# Driving.net
KiCad netlist of a schematic drawn in Altium Designer
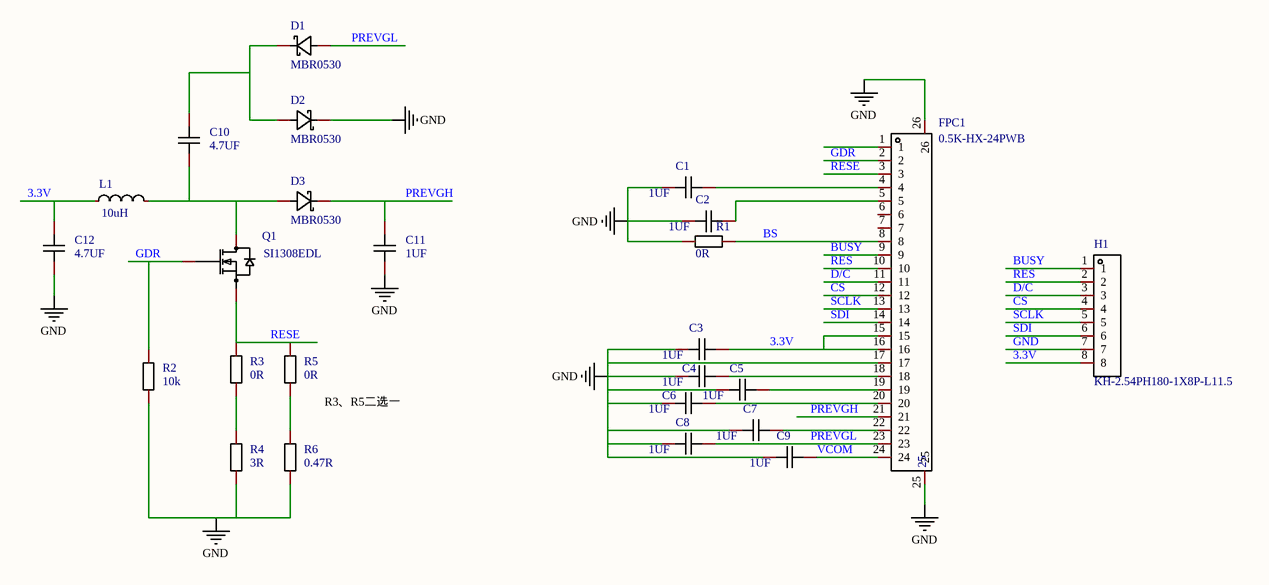
[diagram p0: Driving .schdoc]

(export (version "E")
  (design (tool "Eeschema 10.0.6"))
  (components
    (comp (ref "C1")
      (value "1UF")
      (fields (field (name "NAME") "1UF"))
      (libsource (lib "altium-import") (part "root_0_CAP_0603_"))
    )
    (comp (ref "C2")
      (value "1UF")
      (fields (field (name "NAME") "1UF"))
      (libsource (lib "altium-import") (part "root_0_CAP_0603_"))
    )
    (comp (ref "C3")
      (value "1UF")
      (fields (field (name "NAME") "1UF"))
      (libsource (lib "altium-import") (part "root_0_CAP_0603_"))
    )
    (comp (ref "C4")
      (value "1UF")
      (fields (field (name "NAME") "1UF"))
      (libsource (lib "altium-import") (part "root_0_CAP_0603_"))
    )
    (comp (ref "C5")
      (value "1UF")
      (fields (field (name "NAME") "1UF"))
      (libsource (lib "altium-import") (part "root_0_CAP_0603_"))
    )
    (comp (ref "C6")
      (value "1UF")
      (fields (field (name "NAME") "1UF"))
      (libsource (lib "altium-import") (part "root_0_CAP_0603_"))
    )
    (comp (ref "C7")
      (value "1UF")
      (fields (field (name "NAME") "1UF"))
      (libsource (lib "altium-import") (part "root_0_CAP_0603_"))
    )
    (comp (ref "C8")
      (value "1UF")
      (fields (field (name "NAME") "1UF"))
      (libsource (lib "altium-import") (part "root_0_CAP_0603_"))
    )
    (comp (ref "C9")
      (value "1UF")
      (fields (field (name "NAME") "1UF"))
      (libsource (lib "altium-import") (part "root_0_CAP_0603_"))
    )
    (comp (ref "C10")
      (value "4.7UF")
      (fields (field (name "NAME") "4.7UF"))
      (libsource (lib "altium-import") (part "root_1_CAP_0603_"))
    )
    (comp (ref "C11")
      (value "1UF")
      (fields (field (name "NAME") "1UF"))
      (libsource (lib "altium-import") (part "root_1_CAP_0603_"))
    )
    (comp (ref "C12")
      (value "4.7UF")
      (fields (field (name "NAME") "4.7UF"))
      (libsource (lib "altium-import") (part "root_1_CAP_0603_"))
    )
    (comp (ref "D1")
      (value "MBR0530")
      (description "直流反向耐压(Vr):30V;平均整流电流(Io):500mA;正向压降(Vf):550mV@500mA;")
      (fields (field (name "NAME") "MBR0530") (field (name "MANUFACTURER") "YANGJIE(扬杰)"))
      (libsource (lib "altium-import") (part "root_0_MBR0530_C699108_"))
    )
    (comp (ref "D2")
      (value "MBR0530")
      (description "直流反向耐压(Vr):30V;平均整流电流(Io):500mA;正向压降(Vf):550mV@500mA;")
      (fields (field (name "NAME") "MBR0530") (field (name "MANUFACTURER") "YANGJIE(扬杰)"))
      (libsource (lib "altium-import") (part "root_2_MBR0530_C699108_"))
    )
    (comp (ref "D3")
      (value "MBR0530")
      (description "直流反向耐压(Vr):30V;平均整流电流(Io):500mA;正向压降(Vf):550mV@500mA;")
      (fields (field (name "NAME") "MBR0530") (field (name "MANUFACTURER") "YANGJIE(扬杰)"))
      (libsource (lib "altium-import") (part "root_2_MBR0530_C699108_"))
    )
    (comp (ref "FPC1")
      (value "0.5K-HX-24PWB")
      (description "间距:0.5mm;触点数量:24;锁定特性:翻盖式;安装类型:卧贴;触点类型:双侧触点/上下接;工作温度范围:-55~+85;")
      (fields
        (field (name "NAME") "0.5K-HX-24PWB")
        (field (name "MANUFACTURER") "HDGC(华德共创)")
        (field (name "NAME_1") "25")
      )
      (libsource (lib "altium-import") (part "root_0_0.5K-HX-24PWB_"))
    )
    (comp (ref "H1")
      (value "KH-2.54PH180-1X8P-L11.5")
      (fields (field (name "NAME") "KH-2.54PH180-1X8P-L11.5") (field (name "MANUFACTURER") "kinghelm(金航标)"))
      (libsource (lib "altium-import") (part "root_0_KH-2.54PH180-1X8P-L11.5_"))
    )
    (comp (ref "L1")
      (value "10uH")
      (description "电感值:10uH;精度:±20%;额定电流:1A;直流电阻(DCR):85mΩ;")
      (fields
        (field (name "NAME") "10uH")
        (field (name "MANUFACTURER") "YJYCOIN(益嘉源)")
        (field (name "MANUFACTURER PART") "YNR4026-100M")
      )
      (libsource (lib "altium-import") (part "root_0_YNR4026-100M_"))
    )
    (comp (ref "Q1")
      (value "SI1308EDL")
      (description "类型:N沟道;漏源电压(Vdss):20V;连续漏极电流(Id):4A;导通电阻(RDS(on)@Vgs,Id):36mΩ@10V,4A;")
      (fields (field (name "NAME") "SI1308EDL") (field (name "MANUFACTURER") "VBsemi(微碧)"))
      (libsource (lib "altium-import") (part "root_0_SI1308EDL_"))
    )
    (comp (ref "R1")
      (value "0R")
      (fields (field (name "NAME") "0R"))
      (libsource (lib "altium-import") (part "root_0_Res_0603_"))
    )
    (comp (ref "R2")
      (value "10k")
      (fields (field (name "NAME") "10k"))
      (libsource (lib "altium-import") (part "root_1_Res_0603_"))
    )
    (comp (ref "R3")
      (value "0R")
      (fields (field (name "NAME") "0R"))
      (libsource (lib "altium-import") (part "root_1_Res_0603_"))
    )
    (comp (ref "R4")
      (value "3R")
      (fields (field (name "NAME") "3R"))
      (libsource (lib "altium-import") (part "root_1_Res_0603_"))
    )
    (comp (ref "R5")
      (value "0R")
      (fields (field (name "NAME") "0R"))
      (libsource (lib "altium-import") (part "root_1_Res_0603_"))
    )
    (comp (ref "R6")
      (value "0.47R")
      (fields (field (name "NAME") "0.47R"))
      (libsource (lib "altium-import") (part "root_1_Res_0603_"))
    )
  )
  (nets
    (net (code "1") (name "/3.3V") (class "Default")
      (node (ref "C12") (pin "2") (pinfunction "2_2") (pintype "passive"))
      (node (ref "C3") (pin "2") (pinfunction "2_2") (pintype "passive"))
      (node (ref "FPC1") (pin "15") (pinfunction "15_15") (pintype "passive"))
      (node (ref "FPC1") (pin "16") (pinfunction "16_16") (pintype "passive"))
      (node (ref "H1") (pin "8") (pinfunction "8_8") (pintype "passive"))
      (node (ref "L1") (pin "1") (pinfunction "1_1") (pintype "passive"))
    )
    (net (code "2") (name "/BS") (class "Default")
      (node (ref "FPC1") (pin "8") (pinfunction "8_8") (pintype "passive"))
      (node (ref "R1") (pin "2") (pinfunction "2_2") (pintype "passive"))
    )
    (net (code "3") (name "/BUSY") (class "Default")
      (node (ref "FPC1") (pin "9") (pinfunction "9_9") (pintype "passive"))
      (node (ref "H1") (pin "1") (pinfunction "1_1") (pintype "passive"))
    )
    (net (code "4") (name "/CS") (class "Default")
      (node (ref "FPC1") (pin "12") (pinfunction "12_12") (pintype "passive"))
      (node (ref "H1") (pin "4") (pinfunction "4_4") (pintype "passive"))
    )
    (net (code "5") (name "/D{slash}C") (class "Default")
      (node (ref "FPC1") (pin "11") (pinfunction "11_11") (pintype "passive"))
      (node (ref "H1") (pin "3") (pinfunction "3_3") (pintype "passive"))
    )
    (net (code "6") (name "/GDR") (class "Default")
      (node (ref "FPC1") (pin "2") (pinfunction "2_2") (pintype "passive"))
      (node (ref "Q1") (pin "1") (pinfunction "G_1") (pintype "passive"))
      (node (ref "R2") (pin "2") (pinfunction "2_2") (pintype "passive"))
    )
    (net (code "7") (name "/PREVGH") (class "Default")
      (node (ref "C11") (pin "2") (pinfunction "2_2") (pintype "passive"))
      (node (ref "D3") (pin "1") (pinfunction "K_1") (pintype "passive"))
      (node (ref "FPC1") (pin "21") (pinfunction "21_21") (pintype "passive"))
    )
    (net (code "8") (name "/PREVGL") (class "Default")
      (node (ref "C8") (pin "2") (pinfunction "2_2") (pintype "passive"))
      (node (ref "D1") (pin "2") (pinfunction "A_2") (pintype "passive"))
      (node (ref "FPC1") (pin "23") (pinfunction "23_23") (pintype "passive"))
    )
    (net (code "9") (name "/RES") (class "Default")
      (node (ref "FPC1") (pin "10") (pinfunction "10_10") (pintype "passive"))
      (node (ref "H1") (pin "2") (pinfunction "2_2") (pintype "passive"))
    )
    (net (code "10") (name "/RESE") (class "Default")
      (node (ref "FPC1") (pin "3") (pinfunction "3_3") (pintype "passive"))
      (node (ref "Q1") (pin "2") (pinfunction "S_2") (pintype "passive"))
      (node (ref "R3") (pin "2") (pinfunction "2_2") (pintype "passive"))
      (node (ref "R5") (pin "2") (pinfunction "2_2") (pintype "passive"))
    )
    (net (code "11") (name "/SCLK") (class "Default")
      (node (ref "FPC1") (pin "13") (pinfunction "13_13") (pintype "passive"))
      (node (ref "H1") (pin "5") (pinfunction "5_5") (pintype "passive"))
    )
    (net (code "12") (name "/SDI") (class "Default")
      (node (ref "FPC1") (pin "14") (pinfunction "14_14") (pintype "passive"))
      (node (ref "H1") (pin "6") (pinfunction "6_6") (pintype "passive"))
    )
    (net (code "13") (name "/VCOM") (class "Default")
      (node (ref "C9") (pin "2") (pinfunction "2_2") (pintype "passive"))
      (node (ref "FPC1") (pin "24") (pinfunction "24_24") (pintype "passive"))
    )
    (net (code "14") (name "GND") (class "Default")
      (node (ref "C1") (pin "1") (pinfunction "1_1") (pintype "passive"))
      (node (ref "C11") (pin "1") (pinfunction "1_1") (pintype "passive"))
      (node (ref "C12") (pin "1") (pinfunction "1_1") (pintype "passive"))
      (node (ref "C2") (pin "1") (pinfunction "1_1") (pintype "passive"))
      (node (ref "C3") (pin "1") (pinfunction "1_1") (pintype "passive"))
      (node (ref "C4") (pin "1") (pinfunction "1_1") (pintype "passive"))
      (node (ref "C5") (pin "1") (pinfunction "1_1") (pintype "passive"))
      (node (ref "C6") (pin "1") (pinfunction "1_1") (pintype "passive"))
      (node (ref "C7") (pin "1") (pinfunction "1_1") (pintype "passive"))
      (node (ref "C8") (pin "1") (pinfunction "1_1") (pintype "passive"))
      (node (ref "C9") (pin "1") (pinfunction "1_1") (pintype "passive"))
      (node (ref "D2") (pin "1") (pinfunction "K_1") (pintype "passive"))
      (node (ref "FPC1") (pin "17") (pinfunction "17_17") (pintype "passive"))
      (node (ref "FPC1") (pin "25") (pinfunction "25_25") (pintype "passive"))
      (node (ref "FPC1") (pin "26") (pinfunction "26_26") (pintype "passive"))
      (node (ref "H1") (pin "7") (pinfunction "7_7") (pintype "passive"))
      (node (ref "R1") (pin "1") (pinfunction "1_1") (pintype "passive"))
      (node (ref "R2") (pin "1") (pinfunction "1_1") (pintype "passive"))
      (node (ref "R4") (pin "1") (pinfunction "1_1") (pintype "passive"))
      (node (ref "R6") (pin "1") (pinfunction "1_1") (pintype "passive"))
    )
    (net (code "15") (name "Net-(C1-Pad2)") (class "Default")
      (node (ref "C1") (pin "2") (pinfunction "2_2") (pintype "passive"))
      (node (ref "FPC1") (pin "4") (pinfunction "4_4") (pintype "passive"))
    )
    (net (code "16") (name "Net-(C2-Pad2)") (class "Default")
      (node (ref "C2") (pin "2") (pinfunction "2_2") (pintype "passive"))
      (node (ref "FPC1") (pin "5") (pinfunction "5_5") (pintype "passive"))
    )
    (net (code "17") (name "Net-(C4-Pad2)") (class "Default")
      (node (ref "C4") (pin "2") (pinfunction "2_2") (pintype "passive"))
      (node (ref "FPC1") (pin "18") (pinfunction "18_18") (pintype "passive"))
    )
    (net (code "18") (name "Net-(C5-Pad2)") (class "Default")
      (node (ref "C5") (pin "2") (pinfunction "2_2") (pintype "passive"))
      (node (ref "FPC1") (pin "19") (pinfunction "19_19") (pintype "passive"))
    )
    (net (code "19") (name "Net-(C6-Pad2)") (class "Default")
      (node (ref "C6") (pin "2") (pinfunction "2_2") (pintype "passive"))
      (node (ref "FPC1") (pin "20") (pinfunction "20_20") (pintype "passive"))
    )
    (net (code "20") (name "Net-(C7-Pad2)") (class "Default")
      (node (ref "C7") (pin "2") (pinfunction "2_2") (pintype "passive"))
      (node (ref "FPC1") (pin "22") (pinfunction "22_22") (pintype "passive"))
    )
    (net (code "21") (name "Net-(D1-K)") (class "Default")
      (node (ref "C10") (pin "2") (pinfunction "2_2") (pintype "passive"))
      (node (ref "D1") (pin "1") (pinfunction "K_1") (pintype "passive"))
      (node (ref "D2") (pin "2") (pinfunction "A_2") (pintype "passive"))
    )
    (net (code "22") (name "Net-(D3-A)") (class "Default")
      (node (ref "C10") (pin "1") (pinfunction "1_1") (pintype "passive"))
      (node (ref "D3") (pin "2") (pinfunction "A_2") (pintype "passive"))
      (node (ref "L1") (pin "2") (pinfunction "2_2") (pintype "passive"))
      (node (ref "Q1") (pin "3") (pinfunction "D_3") (pintype "passive"))
    )
    (net (code "23") (name "Net-(R3-Pad1)") (class "Default")
      (node (ref "R3") (pin "1") (pinfunction "1_1") (pintype "passive"))
      (node (ref "R4") (pin "2") (pinfunction "2_2") (pintype "passive"))
    )
    (net (code "24") (name "Net-(R5-Pad1)") (class "Default")
      (node (ref "R5") (pin "1") (pinfunction "1_1") (pintype "passive"))
      (node (ref "R6") (pin "2") (pinfunction "2_2") (pintype "passive"))
    )
    (net (code "25") (name "unconnected-(FPC1-Pad1)") (class "Default")
      (node (ref "FPC1") (pin "1") (pinfunction "1_1") (pintype "passive"))
    )
    (net (code "26") (name "unconnected-(FPC1-Pad6)") (class "Default")
      (node (ref "FPC1") (pin "6") (pinfunction "6_6") (pintype "passive"))
    )
    (net (code "27") (name "unconnected-(FPC1-Pad7)") (class "Default")
      (node (ref "FPC1") (pin "7") (pinfunction "7_7") (pintype "passive"))
    )
  )
)
